# WL_1_2G.net
KiCad netlist of a schematic drawn in Altium Designer
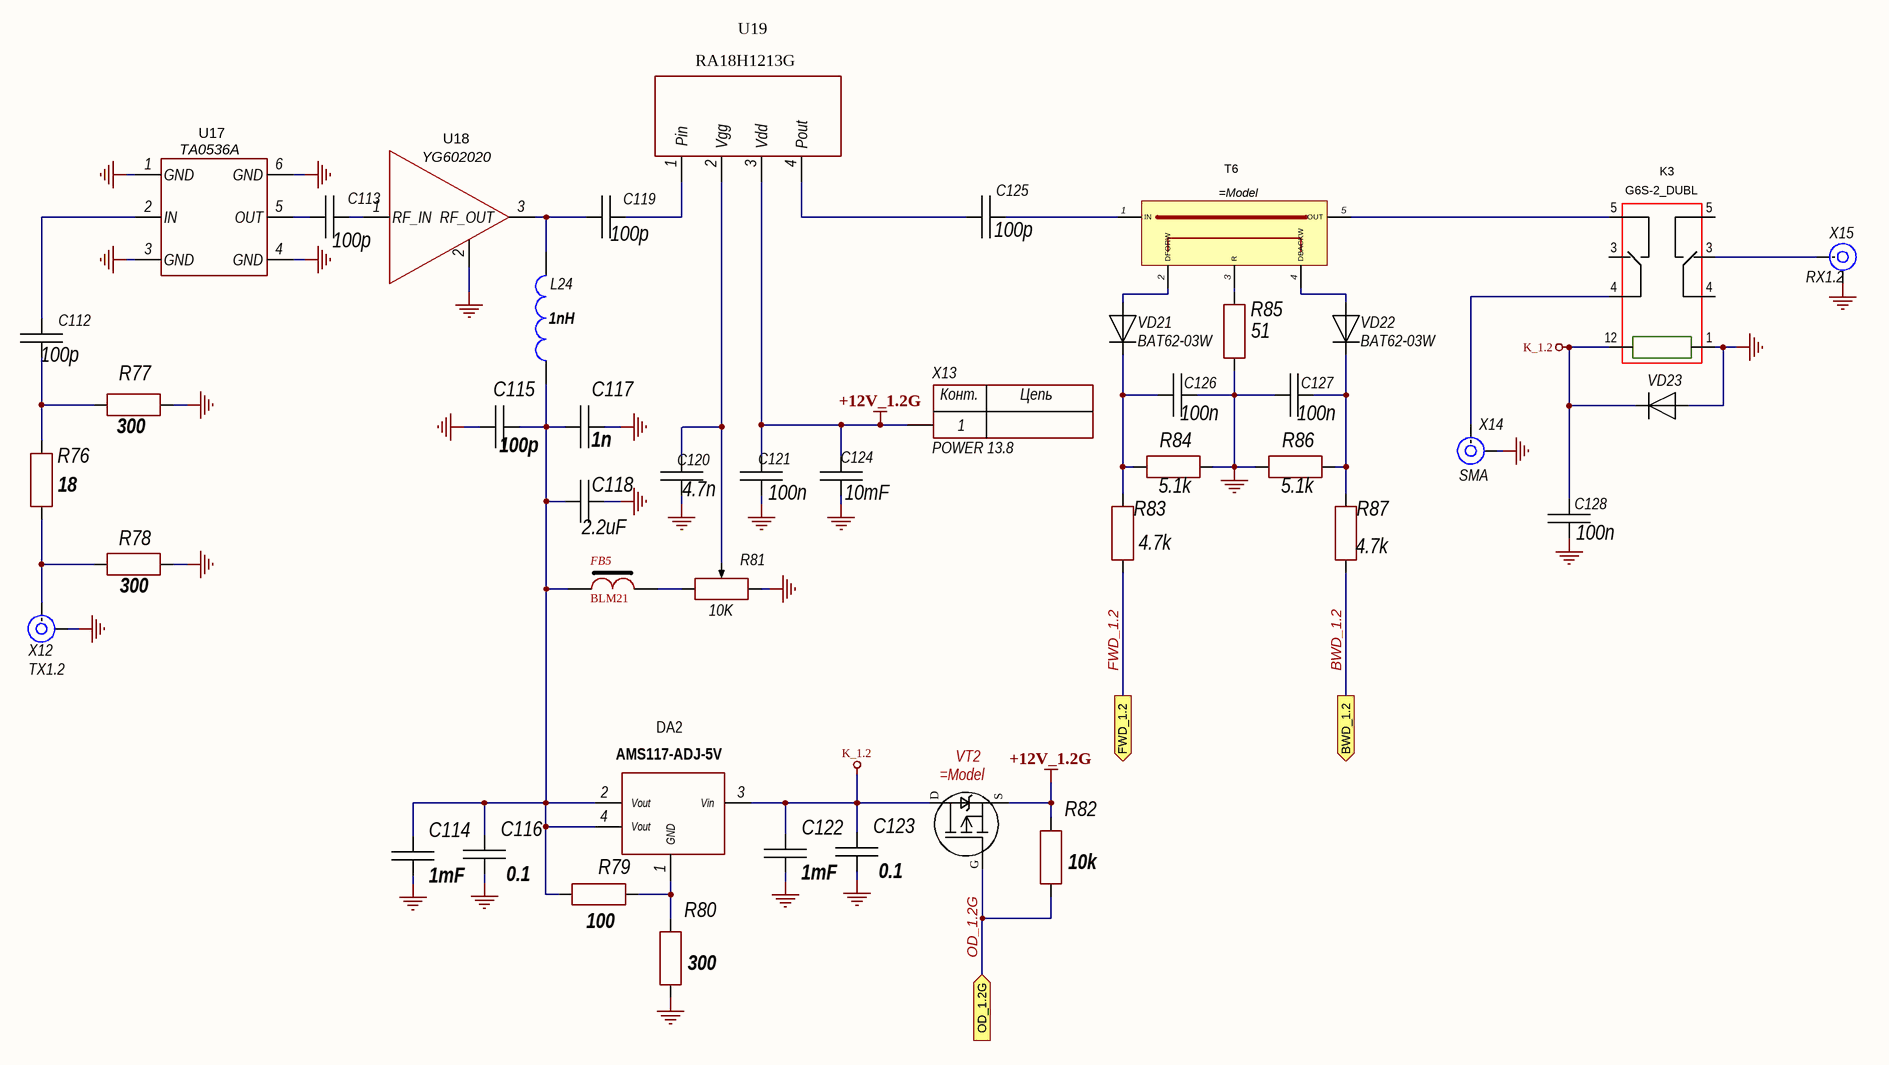
[diagram p0: WL_1.2G.SchDoc]

(export (version "E")
  (design (tool "Eeschema 10.0.6"))
  (components
    (comp (ref "C112")
      (value "100p")
      (footprint "standard:CH0603C")
      (libsource (lib "Discrete") (part "Capacitor"))
    )
    (comp (ref "C113")
      (value "100p")
      (footprint "standard:CH0603C")
      (libsource (lib "Discrete") (part "Capacitor"))
    )
    (comp (ref "C114")
      (value "1mF")
      (footprint "standard:CH0603C")
      (libsource (lib "Discrete") (part "Capacitor"))
    )
    (comp (ref "C115")
      (value "100p")
      (footprint "standard:CH0603C")
      (libsource (lib "Discrete") (part "Capacitor"))
    )
    (comp (ref "C116")
      (value "0.1")
      (footprint "standard:CH0805C")
      (libsource (lib "Discrete") (part "Capacitor"))
    )
    (comp (ref "C117")
      (value "1n")
      (footprint "standard:CH0603C")
      (libsource (lib "Discrete") (part "Capacitor"))
    )
    (comp (ref "C118")
      (value "2.2uF")
      (footprint "standard:CH0603C")
      (libsource (lib "Discrete") (part "Capacitor"))
    )
    (comp (ref "C119")
      (value "100p")
      (footprint "standard:CH0805C")
      (libsource (lib "Discrete") (part "Capacitor"))
    )
    (comp (ref "C120")
      (value "4.7n")
      (footprint "standard:CH0805C")
      (libsource (lib "Discrete") (part "Capacitor"))
    )
    (comp (ref "C121")
      (value "100n")
      (footprint "standard:CH1206C")
      (libsource (lib "Discrete") (part "Capacitor"))
    )
    (comp (ref "C122")
      (value "1mF")
      (footprint "standard:CH0805C")
      (libsource (lib "Discrete") (part "Capacitor"))
    )
    (comp (ref "C123")
      (value "0.1")
      (footprint "standard:CH0805C")
      (libsource (lib "Discrete") (part "Capacitor"))
    )
    (comp (ref "C124")
      (value "10mF")
      (footprint "standard:CH1206C")
      (libsource (lib "Discrete") (part "Capacitor"))
    )
    (comp (ref "C125")
      (value "100p")
      (footprint "standard:CH1210C")
      (libsource (lib "Discrete") (part "Capacitor"))
    )
    (comp (ref "C126")
      (value "100n")
      (footprint "standard:CH0603C")
      (libsource (lib "Discrete") (part "Capacitor"))
    )
    (comp (ref "C127")
      (value "100n")
      (footprint "standard:CH0603C")
      (libsource (lib "Discrete") (part "Capacitor"))
    )
    (comp (ref "C128")
      (value "100n")
      (footprint "standard:CH0805C")
      (libsource (lib "Discrete") (part "Capacitor"))
    )
    (comp (ref "DA2") (value "AMS117-ADJ-5V") (footprint "SOT223") (libsource (lib "Analog") (part "AMS117")))
    (comp (ref "FB5") (value "BLM21") (footprint "CH0805L") (libsource (lib "Discrete") (part "FB-1")))
    (comp (ref "K3")
      (value "G6S-2_DUBL")
      (footprint "G6S-2_DUBL")
      (libsource (lib "Relay") (part "G6S-2_DUBL"))
    )
    (comp (ref "L24")
      (value "1nH")
      (footprint "katuhka")
      (libsource (lib "Transformers") (part "Inductor ring"))
    )
    (comp (ref "R76")
      (value "18")
      (footprint "standard:CH0603R")
      (libsource (lib "Discrete") (part "Resistor"))
    )
    (comp (ref "R77") (value "300") (footprint "standard:CH0603R") (libsource (lib "") (part "Resistor_2")))
    (comp (ref "R78") (value "300") (footprint "standard:CH0603R") (libsource (lib "") (part "Resistor_2")))
    (comp (ref "R79") (value "100") (footprint "standard:CH0805R") (libsource (lib "") (part "Resistor_2")))
    (comp (ref "R80") (value "300") (footprint "standard:CH0805R") (libsource (lib "") (part "Resistor_1")))
    (comp (ref "R81")
      (value "10K")
      (footprint "custom:RES: 3296W")
      (libsource (lib "Discrete") (part "ADJ resistor"))
    )
    (comp (ref "R82") (value "10k") (footprint "standard:CH0805R") (libsource (lib "") (part "Resistor_1")))
    (comp (ref "R83")
      (value "4.7k")
      (footprint "standard:CH0603R")
      (libsource (lib "Discrete") (part "Resistor"))
    )
    (comp (ref "R84") (value "5.1k") (footprint "standard:CH0603R") (libsource (lib "") (part "Resistor_2")))
    (comp (ref "R85") (value "51") (footprint "standard:CH1206R") (libsource (lib "") (part "Resistor_1")))
    (comp (ref "R86") (value "5.1k") (footprint "standard:CH0603R") (libsource (lib "") (part "Resistor_2")))
    (comp (ref "R87")
      (value "4.7k")
      (footprint "standard:CH0603R")
      (libsource (lib "Discrete") (part "Resistor"))
    )
    (comp (ref "T6") (value "~") (footprint "SWR_D") (libsource (lib "Transformers") (part "VHF_KSV1")))
    (comp (ref "U17") (value "TA0536A") (footprint "MA08803") (libsource (lib "Digital") (part "TAU692")))
    (comp (ref "U18")
      (value "YG602020")
      (footprint "SOT89_123")
      (libsource (lib "Digital") (part "YG602020"))
    )
    (comp (ref "U19")
      (value "RA18H1213G")
      (footprint "RA80H1415M1 - duplicate")
      (libsource (lib "Digital") (part "RA80H1415M1"))
    )
    (comp (ref "VD21") (value "BAT62-03W") (footprint "1N4148") (libsource (lib "Diods") (part "Diod")))
    (comp (ref "VD22") (value "BAT62-03W") (footprint "1N4148") (libsource (lib "Diods") (part "Diod")))
    (comp (ref "VD23") (value "~") (footprint "1N4148") (libsource (lib "Diods") (part "Diod")))
    (comp (ref "VT2") (value "~") (footprint "SOT23_132") (libsource (lib "Transistor") (part "P-KANAL")))
    (comp (ref "X12")
      (value "TX1.2")
      (footprint "CON: u.Fl")
      (description "RF")
      (libsource (lib "Connectors") (part "SMA"))
    )
    (comp (ref "X13")
      (value "POWER 13.8")
      (footprint "CON: KNIFE_5MM")
      (libsource (lib "Connectors") (part "1-Connector"))
    )
    (comp (ref "X14")
      (value "SMA")
      (footprint "custom:CON: SMA")
      (description "RF")
      (libsource (lib "Connectors") (part "SMA"))
    )
    (comp (ref "X15")
      (value "RX1.2")
      (footprint "CON: u.Fl")
      (description "RF")
      (libsource (lib "Connectors") (part "SMA"))
    )
  )
  (nets
    (net (code "1") (name "+12V_1.2G") (class "Default")
      (node (ref "C121") (pin "2") (pinfunction "2_2") (pintype "power_in"))
      (node (ref "C124") (pin "2") (pinfunction "2_2") (pintype "power_in"))
      (node (ref "R82") (pin "2") (pinfunction "2_2") (pintype "passive"))
      (node (ref "U19") (pin "3") (pinfunction "Vdd_3") (pintype "passive"))
      (node (ref "VT2") (pin "2") (pinfunction "Исток_2") (pintype "passive"))
      (node (ref "X13") (pin "1") (pinfunction "1_1") (pintype "passive"))
    )
    (net (code "2") (name "/BWD_1.2") (class "Default")
      (node (ref "R87") (pin "2") (pinfunction "2_2") (pintype "passive"))
    )
    (net (code "3") (name "/FWD_1.2") (class "Default")
      (node (ref "R83") (pin "2") (pinfunction "2_2") (pintype "passive"))
    )
    (net (code "4") (name "/OD_1.2G") (class "Default")
      (node (ref "R82") (pin "1") (pinfunction "1_1") (pintype "passive"))
      (node (ref "VT2") (pin "1") (pinfunction "Затвор(Gate)_1") (pintype "passive"))
    )
    (net (code "5") (name "GND") (class "Default")
      (node (ref "C114") (pin "1") (pinfunction "1_1") (pintype "power_in"))
      (node (ref "C115") (pin "2") (pinfunction "2_2") (pintype "power_in"))
      (node (ref "C116") (pin "1") (pinfunction "1_1") (pintype "power_in"))
      (node (ref "C117") (pin "2") (pinfunction "2_2") (pintype "power_in"))
      (node (ref "C118") (pin "2") (pinfunction "2_2") (pintype "power_in"))
      (node (ref "C120") (pin "1") (pinfunction "1_1") (pintype "power_in"))
      (node (ref "C121") (pin "1") (pinfunction "1_1") (pintype "power_in"))
      (node (ref "C122") (pin "1") (pinfunction "1_1") (pintype "power_in"))
      (node (ref "C123") (pin "1") (pinfunction "1_1") (pintype "power_in"))
      (node (ref "C124") (pin "1") (pinfunction "1_1") (pintype "power_in"))
      (node (ref "C126") (pin "1") (pinfunction "1_1") (pintype "power_in"))
      (node (ref "C127") (pin "2") (pinfunction "2_2") (pintype "power_in"))
      (node (ref "C128") (pin "2") (pinfunction "2_2") (pintype "power_in"))
      (node (ref "K3") (pin "1") (pinfunction "1_1") (pintype "passive"))
      (node (ref "R77") (pin "1") (pinfunction "1_1") (pintype "passive"))
      (node (ref "R78") (pin "1") (pinfunction "1_1") (pintype "passive"))
      (node (ref "R80") (pin "1") (pinfunction "1_1") (pintype "passive"))
      (node (ref "R81") (pin "3") (pinfunction "3_3") (pintype "passive"))
      (node (ref "R84") (pin "1") (pinfunction "1_1") (pintype "passive"))
      (node (ref "R85") (pin "1") (pinfunction "1_1") (pintype "passive"))
      (node (ref "R86") (pin "2") (pinfunction "2_2") (pintype "passive"))
      (node (ref "U17") (pin "1") (pinfunction "GND_1") (pintype "passive"))
      (node (ref "U17") (pin "3") (pinfunction "GND_3") (pintype "passive"))
      (node (ref "U17") (pin "4") (pinfunction "GND_4") (pintype "passive"))
      (node (ref "U17") (pin "6") (pinfunction "GND_6") (pintype "passive"))
      (node (ref "U18") (pin "2") (pinfunction "GND_2") (pintype "passive"))
      (node (ref "VD23") (pin "1") (pinfunction "1_1") (pintype "passive"))
      (node (ref "X12") (pin "2") (pinfunction "IN_2") (pintype "passive"))
      (node (ref "X14") (pin "2") (pinfunction "IN_2") (pintype "passive"))
      (node (ref "X15") (pin "2") (pinfunction "IN_2") (pintype "passive"))
    )
    (net (code "6") (name "K_1.2") (class "Default")
      (node (ref "C122") (pin "2") (pinfunction "2_2") (pintype "power_in"))
      (node (ref "C123") (pin "2") (pinfunction "2_2") (pintype "power_in"))
      (node (ref "C128") (pin "1") (pinfunction "1_1") (pintype "power_in"))
      (node (ref "DA2") (pin "3") (pinfunction "Vin_3") (pintype "passive"))
      (node (ref "K3") (pin "12") (pinfunction "12_12") (pintype "passive"))
      (node (ref "VD23") (pin "2") (pinfunction "2_2") (pintype "passive"))
      (node (ref "VT2") (pin "3") (pinfunction "Сток_3") (pintype "passive"))
    )
    (net (code "7") (name "Net-(C112-Pad2)") (class "Default")
      (node (ref "C112") (pin "2") (pinfunction "2_2") (pintype "power_in"))
      (node (ref "R76") (pin "1") (pinfunction "1_1") (pintype "passive"))
      (node (ref "R77") (pin "2") (pinfunction "2_2") (pintype "passive"))
    )
    (net (code "8") (name "Net-(C114-Pad2)") (class "Default")
      (node (ref "C114") (pin "2") (pinfunction "2_2") (pintype "power_in"))
      (node (ref "C115") (pin "1") (pinfunction "1_1") (pintype "power_in"))
      (node (ref "C116") (pin "2") (pinfunction "2_2") (pintype "power_in"))
      (node (ref "C117") (pin "1") (pinfunction "1_1") (pintype "power_in"))
      (node (ref "C118") (pin "1") (pinfunction "1_1") (pintype "power_in"))
      (node (ref "DA2") (pin "2") (pinfunction "Vout_2") (pintype "passive"))
      (node (ref "DA2") (pin "4") (pinfunction "Vout_4") (pintype "passive"))
      (node (ref "FB5") (pin "1") (pinfunction "1_1") (pintype "passive"))
      (node (ref "L24") (pin "2") (pinfunction "2_2") (pintype "passive"))
      (node (ref "R79") (pin "2") (pinfunction "2_2") (pintype "passive"))
    )
    (net (code "9") (name "Net-(C126-Pad2)") (class "Default")
      (node (ref "C126") (pin "2") (pinfunction "2_2") (pintype "power_in"))
      (node (ref "R83") (pin "1") (pinfunction "1_1") (pintype "passive"))
      (node (ref "R84") (pin "2") (pinfunction "2_2") (pintype "passive"))
      (node (ref "VD21") (pin "2") (pinfunction "2_2") (pintype "passive"))
    )
    (net (code "10") (name "Net-(C127-Pad1)") (class "Default")
      (node (ref "C127") (pin "1") (pinfunction "1_1") (pintype "power_in"))
      (node (ref "R86") (pin "1") (pinfunction "1_1") (pintype "passive"))
      (node (ref "R87") (pin "1") (pinfunction "1_1") (pintype "passive"))
      (node (ref "VD22") (pin "2") (pinfunction "2_2") (pintype "passive"))
    )
    (net (code "11") (name "Net-(DA2-GND)") (class "Default")
      (node (ref "DA2") (pin "1") (pinfunction "GND_1") (pintype "passive"))
      (node (ref "R79") (pin "1") (pinfunction "1_1") (pintype "passive"))
      (node (ref "R80") (pin "2") (pinfunction "2_2") (pintype "passive"))
    )
    (net (code "12") (name "Net-(FB5-Pad2)") (class "Default")
      (node (ref "FB5") (pin "2") (pinfunction "2_2") (pintype "passive"))
      (node (ref "R81") (pin "1") (pinfunction "1_1") (pintype "passive"))
    )
    (net (code "13") (name "Net-(K3-Pad3)_1") (class "Default")
      (node (ref "K3") (pin "3") (pinfunction "3_3") (pintype "passive"))
      (node (ref "X15") (pin "1") (pinfunction "IN_1") (pintype "passive"))
    )
    (net (code "14") (name "Net-(K3-Pad4)") (class "Default")
      (node (ref "K3") (pin "4") (pinfunction "4_4") (pintype "passive"))
      (node (ref "X14") (pin "1") (pinfunction "IN_1") (pintype "passive"))
    )
    (net (code "15") (name "Net-(R76-Pad2)") (class "Default")
      (node (ref "R76") (pin "2") (pinfunction "2_2") (pintype "passive"))
      (node (ref "R78") (pin "2") (pinfunction "2_2") (pintype "passive"))
      (node (ref "X12") (pin "1") (pinfunction "IN_1") (pintype "passive"))
    )
    (net (code "16") (name "Net-(T6-DBACKW)") (class "Default")
      (node (ref "T6") (pin "4") (pinfunction "DBACKW_4") (pintype "passive"))
      (node (ref "VD22") (pin "1") (pinfunction "1_1") (pintype "passive"))
    )
    (net (code "17") (name "Net-(T6-DFORW)") (class "Default")
      (node (ref "T6") (pin "2") (pinfunction "DFORW_2") (pintype "passive"))
      (node (ref "VD21") (pin "1") (pinfunction "1_1") (pintype "passive"))
    )
    (net (code "18") (name "Net-(T6-IN)") (class "Default")
      (node (ref "C125") (pin "1") (pinfunction "1_1") (pintype "power_in"))
      (node (ref "T6") (pin "1") (pinfunction "IN_1") (pintype "passive"))
    )
    (net (code "19") (name "Net-(T6-OUT)") (class "Default")
      (node (ref "K3") (pin "5") (pinfunction "5_5") (pintype "passive"))
      (node (ref "T6") (pin "5") (pinfunction "OUT_5") (pintype "passive"))
    )
    (net (code "20") (name "Net-(T6-R)") (class "Default")
      (node (ref "R85") (pin "2") (pinfunction "2_2") (pintype "passive"))
      (node (ref "T6") (pin "3") (pinfunction "R_3") (pintype "passive"))
    )
    (net (code "21") (name "Net-(U17-IN)") (class "Default")
      (node (ref "C112") (pin "1") (pinfunction "1_1") (pintype "power_in"))
      (node (ref "U17") (pin "2") (pinfunction "IN_2") (pintype "passive"))
    )
    (net (code "22") (name "Net-(U17-OUT)") (class "Default")
      (node (ref "C113") (pin "2") (pinfunction "2_2") (pintype "power_in"))
      (node (ref "U17") (pin "5") (pinfunction "OUT_5") (pintype "passive"))
    )
    (net (code "23") (name "Net-(U18-RF_IN)") (class "Default")
      (node (ref "C113") (pin "1") (pinfunction "1_1") (pintype "power_in"))
      (node (ref "U18") (pin "1") (pinfunction "RF_IN_1") (pintype "passive"))
    )
    (net (code "24") (name "Net-(U18-RF_OUT)") (class "Default")
      (node (ref "C119") (pin "2") (pinfunction "2_2") (pintype "power_in"))
      (node (ref "L24") (pin "1") (pinfunction "1_1") (pintype "passive"))
      (node (ref "U18") (pin "3") (pinfunction "RF_OUT_3") (pintype "passive"))
    )
    (net (code "25") (name "Net-(U19-Pin)") (class "Default")
      (node (ref "C119") (pin "1") (pinfunction "1_1") (pintype "power_in"))
      (node (ref "U19") (pin "1") (pinfunction "Pin_1") (pintype "passive"))
    )
    (net (code "26") (name "Net-(U19-Pout)") (class "Default")
      (node (ref "C125") (pin "2") (pinfunction "2_2") (pintype "power_in"))
      (node (ref "U19") (pin "4") (pinfunction "Pout_4") (pintype "passive"))
    )
    (net (code "27") (name "Net-(U19-Vgg)") (class "Default")
      (node (ref "C120") (pin "2") (pinfunction "2_2") (pintype "power_in"))
      (node (ref "R81") (pin "2") (pinfunction "2_2") (pintype "passive"))
      (node (ref "U19") (pin "2") (pinfunction "Vgg_2") (pintype "passive"))
    )
    (net (code "28") (name "unconnected-(K3-Pad3)") (class "Default")
      (node (ref "K3") (pin "3") (pinfunction "3_3") (pintype "passive"))
    )
    (net (code "29") (name "unconnected-(K3-Pad4)_1") (class "Default")
      (node (ref "K3") (pin "4") (pinfunction "4_4") (pintype "passive"))
    )
    (net (code "30") (name "unconnected-(K3-Pad5)") (class "Default")
      (node (ref "K3") (pin "5") (pinfunction "5_5") (pintype "passive"))
    )
  )
)
